# HA_Power.net
KiCad netlist of a schematic drawn in Altium Designer
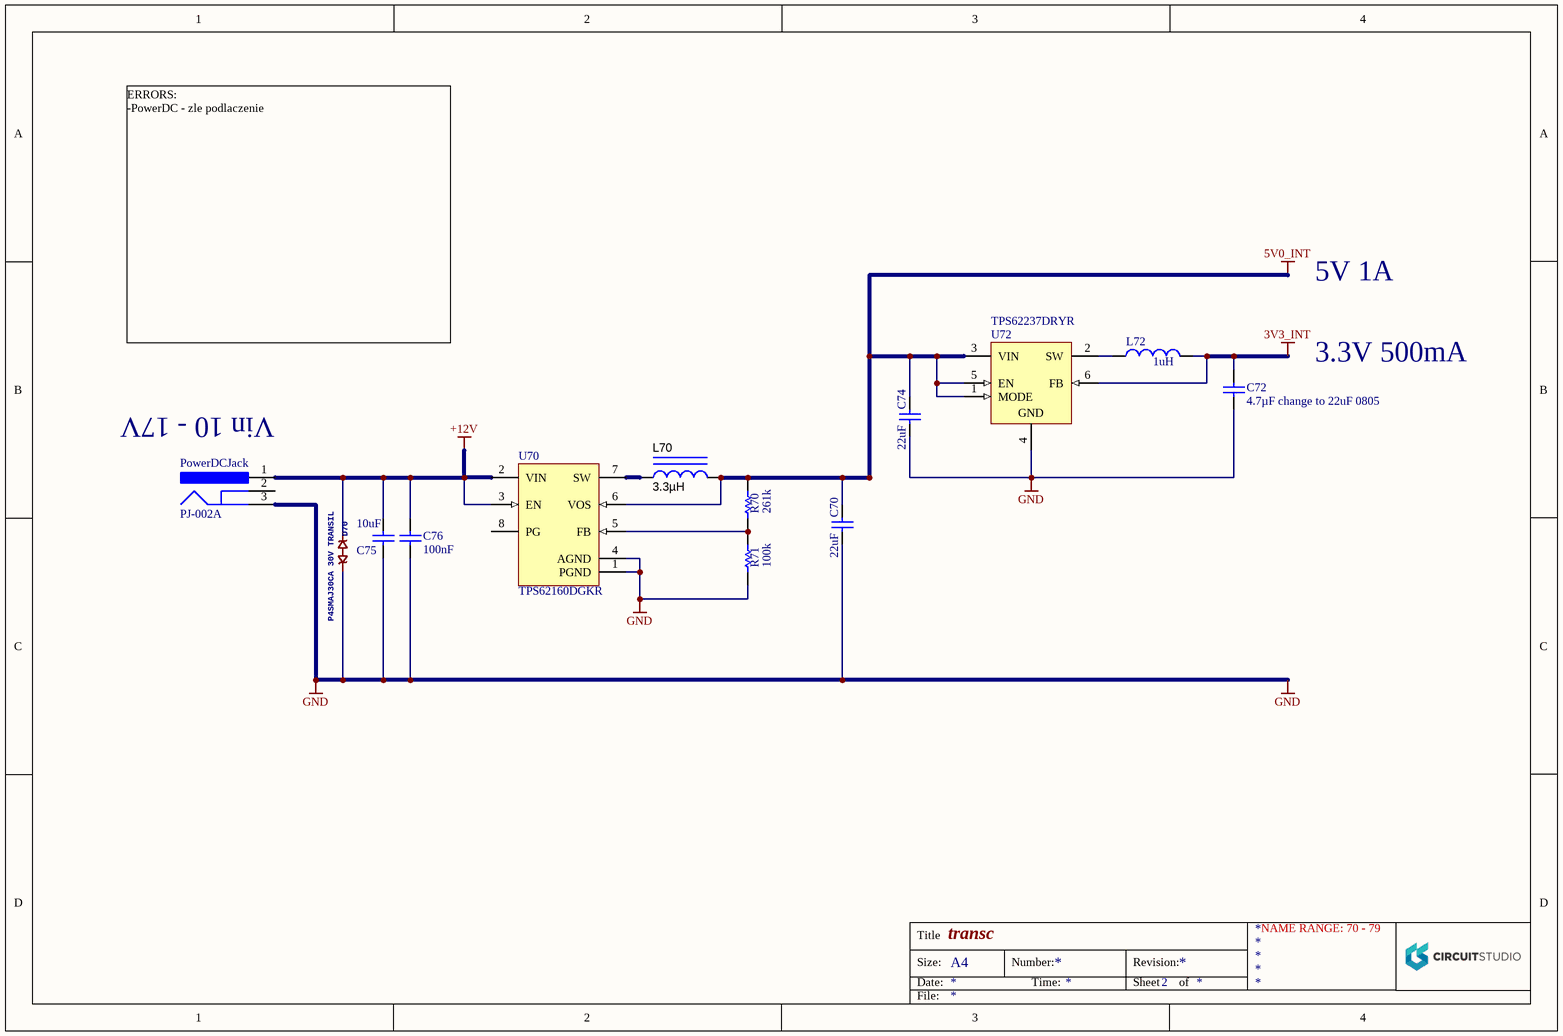
[diagram p0: HA_Power.SchDoc]

(export (version "E")
  (design (tool "Eeschema 10.0.6"))
  (components
    (comp (ref "C70")
      (value "22uF")
      (footprint "CAPC0805(2012)75_N")
      (fields (field (name "TOLERANCE") "±10%") (field (name "Comment") "22uF 10V"))
      (libsource (lib "Altium Content Vault") (part "CMP-1036-00417-1"))
    )
    (comp (ref "C72")
      (value "4.7uF CL10B475KQ8NQNC")
      (footprint "CAPC1608X95X30NL15T20")
      (fields
        (field (name "CAPACITANCE") "4.7µF change to 22uF 0805")
        (field (name "TOLERANCE") "±10%")
        (field (name "MANUFACTURER") "Samsung Electro-Mechanics")
      )
      (libsource (lib "Altium Content Vault") (part "CMP-2000-06096-1"))
    )
    (comp (ref "C74")
      (value "22uF")
      (footprint "CAPC0805(2012)75_N")
      (fields (field (name "TOLERANCE") "±10%") (field (name "Comment") "22uF 10V"))
      (libsource (lib "Altium Content Vault") (part "CMP-1036-00417-1"))
    )
    (comp (ref "C75")
      (value "10uF")
      (footprint "CAPC1206(3216)190_N")
      (description "CAP 1206 (3216 Metric) Thickness 1.9mm SMD")
      (fields (field (name "TOLERANCE") "Â±20%") (field (name "Comment") "10uF 35V"))
      (libsource (lib "Altium Content Vault") (part "CMP-1037-04990-1"))
    )
    (comp (ref "C76")
      (value "100nF")
      (footprint "CAPC0603(1608)100_L")
      (description "CAP 100nF 100V ±10% 0603 (1608 Metric) Thickness 1mm SMD")
      (fields (field (name "TOLERANCE") "±10%") (field (name "Comment") "100nF 100V"))
      (libsource (lib "Altium Content Vault") (part "CMP-1035-00529-1"))
    )
    (comp (ref "D70")
      (value "P4SMAJ30CA 30V TRANSIL")
      (footprint "DO214AC_BIDIR")
      (libsource (lib "mms") (part "DIODE_BIDIR-DO214AC"))
    )
    (comp (ref "L70")
      (value "3.3uH XPL2010-332MLB")
      (footprint "XPL2010")
      (description "XPL2010 Inductor")
      (fields
        (field (name "PARTNUMBER") "XPL2010-332MLB")
        (field (name "MANUFACTURER") "Coilcraft")
        (field (name "VALUEDISPLAYED") "3.3µH")
        (field (name "PUBLISHER") "Texas Instruments")
      )
      (libsource (lib "Inductor_Coilcraft") (part "XPL2010-332MLB"))
    )
    (comp (ref "L72")
      (value "LQM21PN2R2MC0D")
      (footprint "MURA-IND0805_H_0.55_M")
      (description "Chip Inductor, 1.0 uH, +/- 20%, -55 to 125 degC, 2-Pin SMD (0805), RoHS, Tape and Reel")
      (fields (field (name "MANUFACTURER") "Murata") (field (name "INDUCTANCE") "1uH"))
      (libsource (lib "Altium Content Vault") (part "CMP-2000-06589-1"))
    )
    (comp (ref "PowerDCJack")
      (value "PJ-002A")
      (footprint "CUI-PJ-002A_V")
      (fields (field (name "MANUFACTURER") "CUIInc."))
      (libsource (lib "Altium Content Vault") (part "JACK-2CD3-RN"))
    )
    (comp (ref "R70")
      (value "261k")
      (footprint "RESC0603(1608)_N")
      (description "1% 0603 SMD")
      (fields (field (name "TOLERANCE") "1 %"))
      (libsource (lib "Altium Content Vault") (part "CMP-1012-00122-1"))
    )
    (comp (ref "R71")
      (value "100k")
      (footprint "RESC0603(1608)_N")
      (description "1% 0603 SMD")
      (fields (field (name "TOLERANCE") "1 %"))
      (libsource (lib "Altium Content Vault") (part "CMP-1012-00122-1"))
    )
    (comp (ref "U70")
      (value "TPS62160DGKR")
      (footprint "DGK8_N")
      (fields (field (name "MANUFACTURER") "Texas Instruments"))
      (libsource (lib "Altium Content Vault") (part "CMP-0323-00440-1"))
    )
    (comp (ref "U72")
      (value "TPS62237DRYR")
      (footprint "DRY0006A")
      (fields (field (name "MANUFACTURER") "Texas Instruments"))
      (libsource (lib "Altium Content Vault") (part "CMP-0323-00243-3"))
    )
  )
  (nets
    (net (code "1") (name "+12V") (class "Default")
      (node (ref "C75") (pin "2") (pinfunction "2_2") (pintype "passive"))
      (node (ref "C76") (pin "1") (pinfunction "1_1") (pintype "passive"))
      (node (ref "D70") (pin "2") (pinfunction "2_2") (pintype "passive"))
      (node (ref "PowerDCJack") (pin "1") (pinfunction "1_1") (pintype "passive"))
      (node (ref "U70") (pin "2") (pinfunction "VIN_2") (pintype "power_in"))
      (node (ref "U70") (pin "3") (pinfunction "EN_3") (pintype "input"))
    )
    (net (code "2") (name "3V3_INT") (class "Default")
      (node (ref "C72") (pin "2") (pinfunction "2_2") (pintype "passive"))
      (node (ref "L72") (pin "2") (pinfunction "2_2") (pintype "passive"))
      (node (ref "U72") (pin "6") (pinfunction "FB_6") (pintype "input"))
    )
    (net (code "3") (name "5V0_INT") (class "Default")
      (node (ref "C70") (pin "2") (pinfunction "2_2") (pintype "passive"))
      (node (ref "C74") (pin "2") (pinfunction "2_2") (pintype "passive"))
      (node (ref "L70") (pin "2") (pinfunction "2_2") (pintype "passive"))
      (node (ref "R70") (pin "2") (pinfunction "2_2") (pintype "passive"))
      (node (ref "U70") (pin "6") (pinfunction "VOS_6") (pintype "input"))
      (node (ref "U72") (pin "1") (pinfunction "MODE_1") (pintype "input"))
      (node (ref "U72") (pin "3") (pinfunction "VIN_3") (pintype "power_in"))
      (node (ref "U72") (pin "5") (pinfunction "EN_5") (pintype "input"))
    )
    (net (code "4") (name "GND") (class "Default")
      (node (ref "C70") (pin "1") (pinfunction "1_1") (pintype "passive"))
      (node (ref "C72") (pin "1") (pinfunction "1_1") (pintype "passive"))
      (node (ref "C74") (pin "1") (pinfunction "1_1") (pintype "passive"))
      (node (ref "C75") (pin "1") (pinfunction "1_1") (pintype "passive"))
      (node (ref "C76") (pin "2") (pinfunction "2_2") (pintype "passive"))
      (node (ref "D70") (pin "1") (pinfunction "1_1") (pintype "passive"))
      (node (ref "PowerDCJack") (pin "3") (pinfunction "3_3") (pintype "passive"))
      (node (ref "R71") (pin "1") (pinfunction "1_1") (pintype "passive"))
      (node (ref "U70") (pin "1") (pinfunction "PGND_1") (pintype "power_in"))
      (node (ref "U70") (pin "4") (pinfunction "AGND_4") (pintype "power_in"))
      (node (ref "U72") (pin "4") (pinfunction "GND_4") (pintype "power_in"))
    )
    (net (code "5") (name "Net-(U70-FB)") (class "Default")
      (node (ref "R70") (pin "1") (pinfunction "1_1") (pintype "passive"))
      (node (ref "R71") (pin "2") (pinfunction "2_2") (pintype "passive"))
      (node (ref "U70") (pin "5") (pinfunction "FB_5") (pintype "input"))
    )
    (net (code "6") (name "Net-(U70-SW)") (class "Default")
      (node (ref "L70") (pin "1") (pinfunction "1_1") (pintype "passive"))
      (node (ref "U70") (pin "7") (pinfunction "SW_7") (pintype "power_in"))
    )
    (net (code "7") (name "Net-(U72-SW)") (class "Default")
      (node (ref "L72") (pin "1") (pinfunction "1_1") (pintype "passive"))
      (node (ref "U72") (pin "2") (pinfunction "SW_2") (pintype "power_in"))
    )
    (net (code "8") (name "unconnected-(PowerDCJack-Pad2)") (class "Default")
      (node (ref "PowerDCJack") (pin "2") (pinfunction "2_2") (pintype "passive"))
    )
    (net (code "9") (name "unconnected-(U70-PG-Pad8)") (class "Default")
      (node (ref "U70") (pin "8") (pinfunction "PG_8") (pintype "tri_state"))
    )
  )
)
